# FAN.net
KiCad netlist of a schematic drawn in Altium Designer
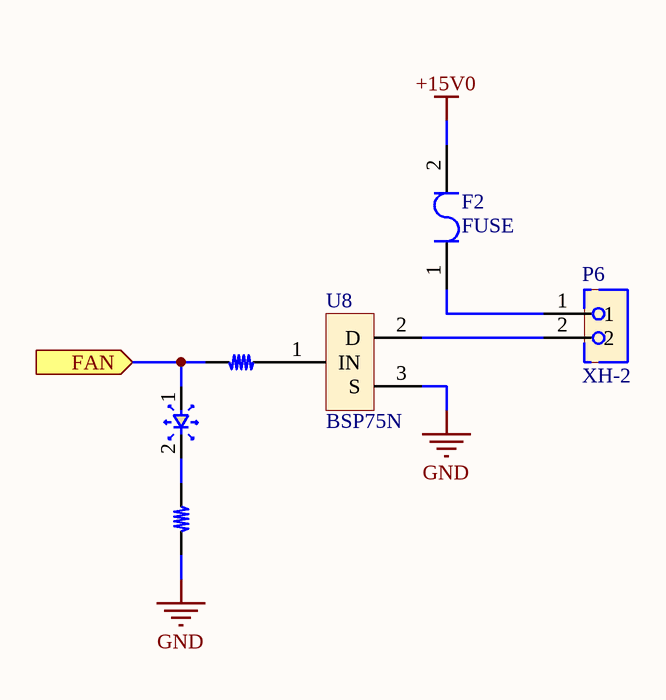
[diagram p0: FAN.SchDoc]

(export (version "E")
  (design (tool "Eeschema 10.0.6"))
  (components
    (comp (ref "D20")
      (value "LED_SMD")
      (footprint "D 0603")
      (libsource (lib "radmehr_library") (part "LED_SMD"))
    )
    (comp (ref "F2") (value "FUSE") (footprint "F 1812") (libsource (lib "radmehr_library") (part "FUSE")))
    (comp (ref "P6") (value "XH-2") (footprint "XH-2") (libsource (lib "radmehr_library") (part "XH-2")))
    (comp (ref "R51")
      (value "RES_SMD")
      (footprint "R 0603")
      (libsource (lib "radmehr_library") (part "RES_SMD"))
    )
    (comp (ref "R52")
      (value "RES_SMD")
      (footprint "R 0603")
      (libsource (lib "radmehr_library") (part "RES_SMD"))
    )
    (comp (ref "U8")
      (value "BSP75N")
      (footprint "SOT-223 - BSP75N")
      (libsource (lib "radmehr_library") (part "BSP75N"))
    )
  )
  (nets
    (net (code "1") (name "+15V0") (class "Default") (node (ref "F2") (pin "2") (pintype "passive")))
    (net (code "2") (name "/FAN") (class "Default")
      (node (ref "D20") (pin "1") (pintype "passive"))
      (node (ref "R51") (pin "2") (pinfunction "2_2") (pintype "passive"))
    )
    (net (code "3") (name "GND") (class "Default")
      (node (ref "R52") (pin "2") (pinfunction "2_2") (pintype "passive"))
      (node (ref "U8") (pin "3") (pinfunction "S_3") (pintype "power_in"))
    )
    (net (code "4") (name "Net-(D20-Pad2)") (class "Default")
      (node (ref "D20") (pin "2") (pintype "passive"))
      (node (ref "R52") (pin "1") (pinfunction "1_1") (pintype "passive"))
    )
    (net (code "5") (name "Net-(F2-Pad1)") (class "Default")
      (node (ref "F2") (pin "1") (pintype "passive"))
      (node (ref "P6") (pin "1") (pinfunction "1_1") (pintype "passive"))
    )
    (net (code "6") (name "Net-(U8-D)") (class "Default")
      (node (ref "P6") (pin "2") (pinfunction "2_2") (pintype "passive"))
      (node (ref "U8") (pin "2") (pinfunction "D_2") (pintype "power_in"))
    )
    (net (code "7") (name "Net-(U8-IN)") (class "Default")
      (node (ref "R51") (pin "1") (pinfunction "1_1") (pintype "passive"))
      (node (ref "U8") (pin "1") (pinfunction "IN_1") (pintype "power_in"))
    )
  )
)
